# OLED-Pi_EH.net
KiCad netlist of a schematic drawn in EAGLE
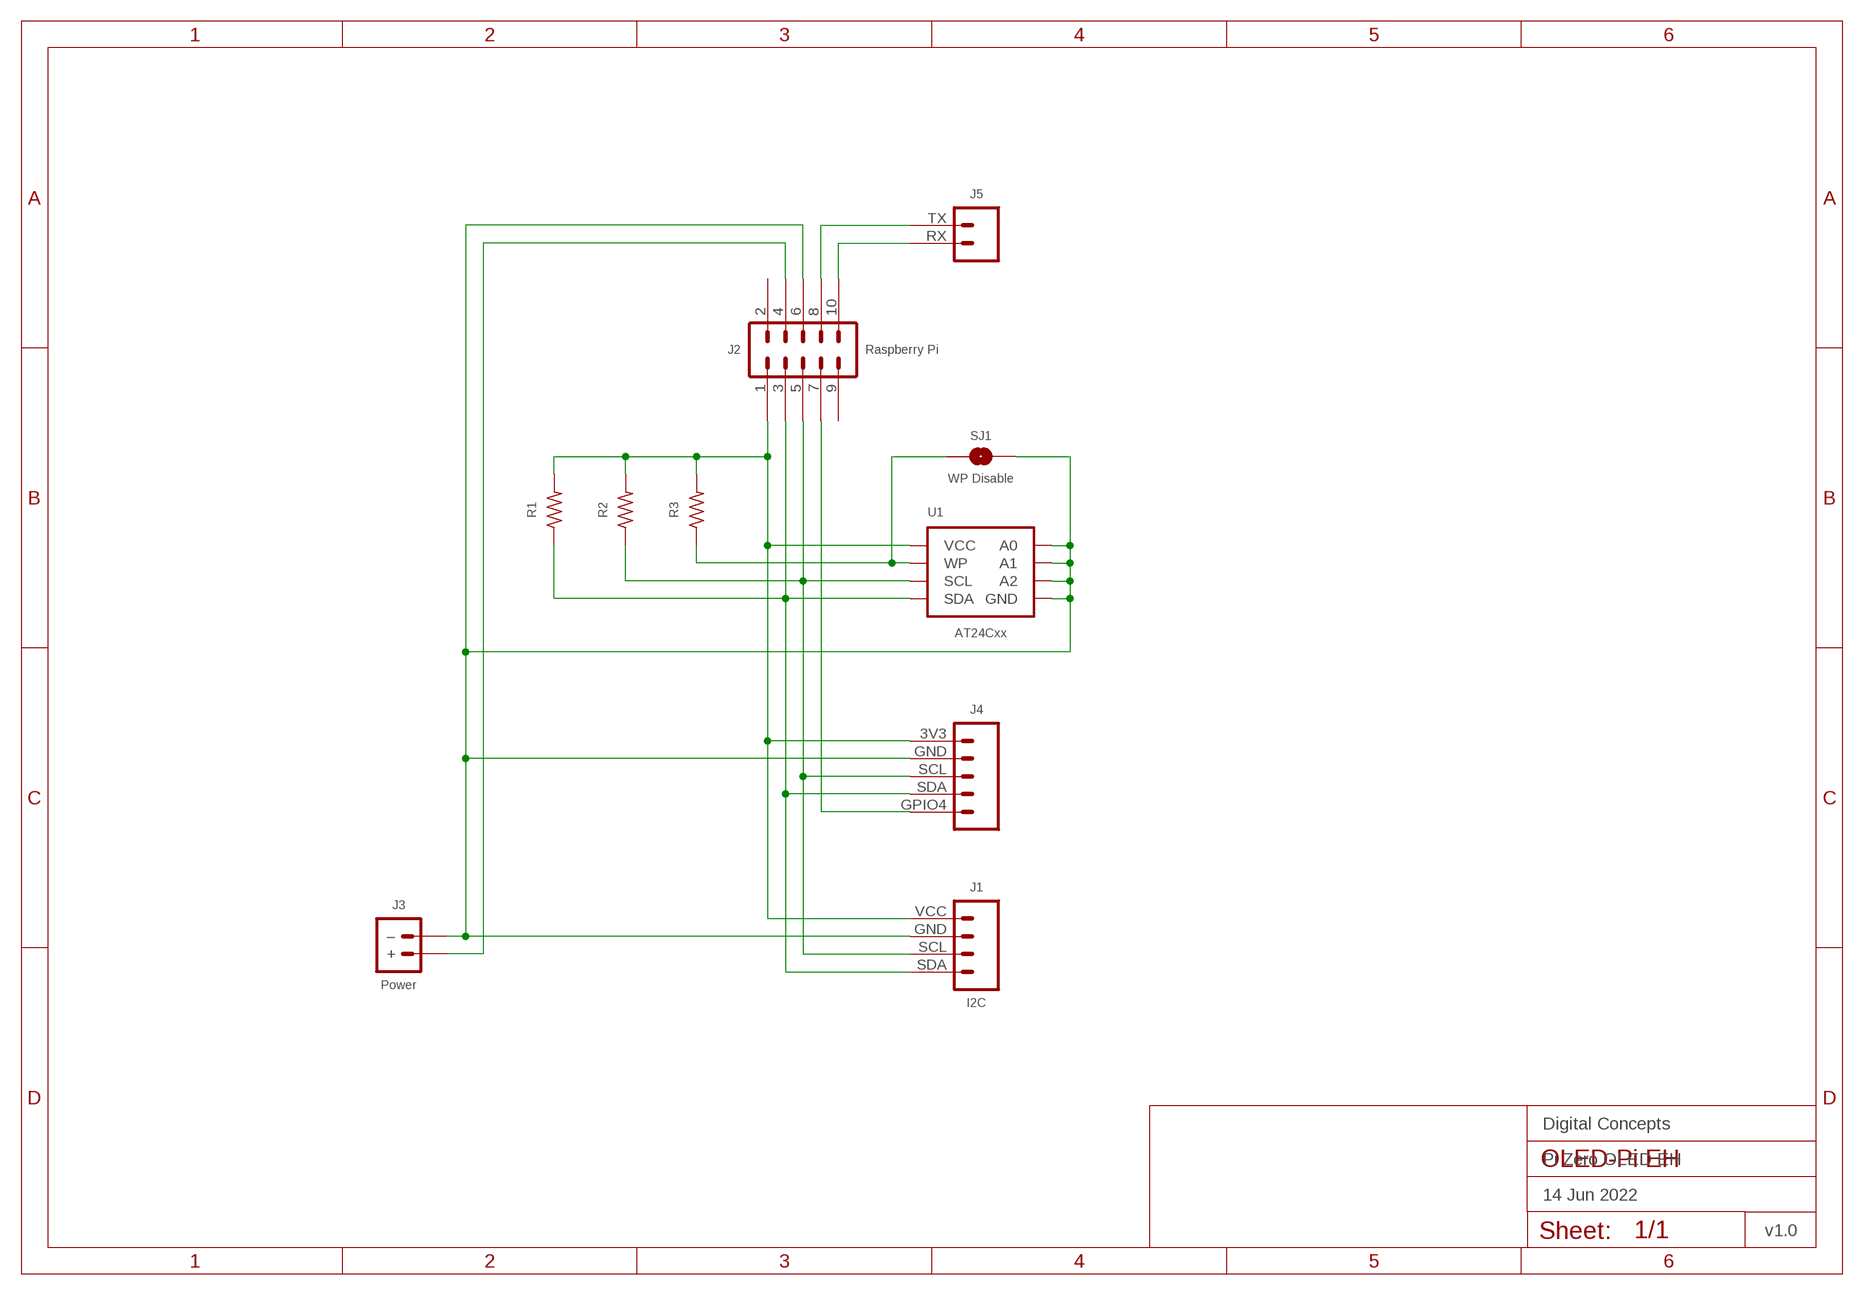
[diagram p0: schematic, sheet 1]

(export (version "E")
  (design (tool "Eeschema 10.0.6"))
  (components
    (comp (ref "J1")
      (value "I2C")
      (footprint "eagle-import:CONN_04-I2C")
      (libsource (lib "eagle-import") (part "HEADER-1X4-I2C"))
    )
    (comp (ref "J2")
      (value "Raspberry Pi")
      (footprint "eagle-import:CONN_2X5-PI-1")
      (libsource (lib "eagle-import") (part "HEADER-2X5-PI-1"))
    )
    (comp (ref "J3")
      (value "Power")
      (footprint "eagle-import:JST-PH2.0-2-HORIZONTAL-POWER")
      (libsource (lib "eagle-import") (part "JST-PH2.0-2-HORIZONTAL-POWERJST-PTH-2"))
    )
    (comp (ref "J4")
      (value "JST-PH2.0-5-HORIZONTAL-OLED-PI")
      (footprint "eagle-import:JST-PH2.0-5-HORIZONTAL-OLED-PI")
      (libsource (lib "eagle-import") (part "JST-PH2.0-5-HORIZONTAL-OLED-PI"))
    )
    (comp (ref "J5")
      (value "JST-PH2.0-2-HORIZONTAL-TX-RXJST-PTH-2")
      (footprint "eagle-import:JST-PH2.0-2-HORIZONTAL=TX-RX")
      (libsource (lib "eagle-import") (part "JST-PH2.0-2-HORIZONTAL-TX-RXJST-PTH-2"))
    )
    (comp (ref "R1")
      (value "RESISTORR0805")
      (footprint "eagle-import:R0805")
      (libsource (lib "eagle-import") (part "RESISTORR0805"))
    )
    (comp (ref "R2")
      (value "RESISTORR0805")
      (footprint "eagle-import:R0805")
      (libsource (lib "eagle-import") (part "RESISTORR0805"))
    )
    (comp (ref "R3")
      (value "RESISTORR0805")
      (footprint "eagle-import:R0805")
      (libsource (lib "eagle-import") (part "RESISTORR0805"))
    )
    (comp (ref "SJ1")
      (value "WP Disable")
      (footprint "eagle-import:SJ")
      (libsource (lib "eagle-import") (part "SJ"))
    )
    (comp (ref "U1")
      (value "AT24Cxx")
      (footprint "eagle-import:SOP-8")
      (libsource (lib "eagle-import") (part "AT24CXX-EEPROM"))
    )
  )
  (nets
    (net (code "1") (name "Net-(J1-1)") (class "Default")
      (node (ref "J1") (pin "VCC") (pinfunction "1_VCC") (pintype "passive"))
      (node (ref "J2") (pin "1") (pinfunction "1_1") (pintype "passive"))
      (node (ref "J4") (pin "3V3") (pinfunction "1_3V3") (pintype "passive"))
      (node (ref "R1") (pin "2") (pinfunction "2_2") (pintype "passive"))
      (node (ref "R2") (pin "2") (pinfunction "2_2") (pintype "passive"))
      (node (ref "R3") (pin "2") (pinfunction "2_2") (pintype "passive"))
      (node (ref "U1") (pin "P$8") (pinfunction "VCC_P$8") (pintype "bidirectional"))
    )
    (net (code "2") (name "Net-(J1-2)") (class "Default")
      (node (ref "J1") (pin "GND") (pinfunction "2_GND") (pintype "passive"))
      (node (ref "J2") (pin "6") (pinfunction "8_6") (pintype "passive"))
      (node (ref "J3") (pin "-") (pinfunction "–_-") (pintype "power_in"))
      (node (ref "J4") (pin "GND") (pinfunction "2_GND") (pintype "passive"))
      (node (ref "SJ1") (pin "2") (pinfunction "2_2") (pintype "passive"))
      (node (ref "U1") (pin "P$1") (pinfunction "A0_P$1") (pintype "bidirectional"))
      (node (ref "U1") (pin "P$2") (pinfunction "A1_P$2") (pintype "bidirectional"))
      (node (ref "U1") (pin "P$3") (pinfunction "A2_P$3") (pintype "bidirectional"))
      (node (ref "U1") (pin "P$4") (pinfunction "GND_P$4") (pintype "bidirectional"))
    )
    (net (code "3") (name "Net-(J1-3)") (class "Default")
      (node (ref "J1") (pin "SCL") (pinfunction "3_SCL") (pintype "passive"))
      (node (ref "J2") (pin "5") (pinfunction "3_5") (pintype "passive"))
      (node (ref "J4") (pin "SCL") (pinfunction "3_SCL") (pintype "passive"))
      (node (ref "R2") (pin "1") (pinfunction "1_1") (pintype "passive"))
      (node (ref "U1") (pin "P$6") (pinfunction "SCL_P$6") (pintype "bidirectional"))
    )
    (net (code "4") (name "Net-(J1-4)") (class "Default")
      (node (ref "J1") (pin "SDA") (pinfunction "4_SDA") (pintype "passive"))
      (node (ref "J2") (pin "3") (pinfunction "2_3") (pintype "passive"))
      (node (ref "J4") (pin "SDA") (pinfunction "4_SDA") (pintype "passive"))
      (node (ref "R1") (pin "1") (pinfunction "1_1") (pintype "passive"))
      (node (ref "U1") (pin "P$5") (pinfunction "SDA_P$5") (pintype "bidirectional"))
    )
    (net (code "5") (name "Net-(J2-4)") (class "Default")
      (node (ref "J2") (pin "7") (pinfunction "4_7") (pintype "passive"))
      (node (ref "J4") (pin "GPIO4") (pinfunction "5_GPIO4") (pintype "passive"))
    )
    (net (code "6") (name "Net-(J2-6)") (class "Default")
      (node (ref "J2") (pin "10") (pinfunction "6_10") (pintype "passive"))
      (node (ref "J5") (pin "RX") (pinfunction "2_RX") (pintype "passive"))
    )
    (net (code "7") (name "Net-(J2-7)") (class "Default")
      (node (ref "J2") (pin "8") (pinfunction "7_8") (pintype "passive"))
      (node (ref "J5") (pin "TX") (pinfunction "1_TX") (pintype "passive"))
    )
    (net (code "8") (name "Net-(J2-9)") (class "Default")
      (node (ref "J2") (pin "4") (pinfunction "9_4") (pintype "passive"))
      (node (ref "J3") (pin "+") (pinfunction "+_+") (pintype "power_in"))
    )
    (net (code "9") (name "Net-(U1-WP)") (class "Default")
      (node (ref "R3") (pin "1") (pinfunction "1_1") (pintype "passive"))
      (node (ref "SJ1") (pin "1") (pinfunction "1_1") (pintype "passive"))
      (node (ref "U1") (pin "P$7") (pinfunction "WP_P$7") (pintype "bidirectional"))
    )
    (net (code "10") (name "unconnected-(J2-5-Pad9)") (class "Default")
      (node (ref "J2") (pin "9") (pinfunction "5_9") (pintype "passive"))
    )
    (net (code "11") (name "unconnected-(J2-10-Pad2)") (class "Default")
      (node (ref "J2") (pin "2") (pinfunction "10_2") (pintype "passive"))
    )
  )
)
